# UART_to_RS232.net
KiCad netlist of a schematic drawn in EAGLE
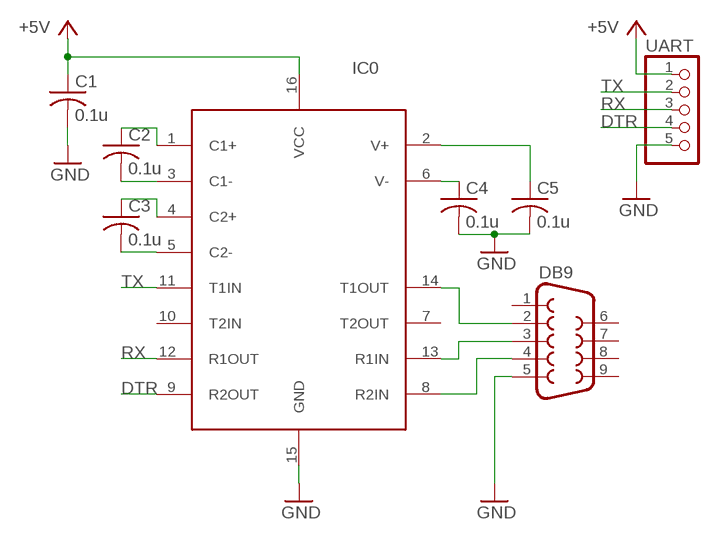
[diagram p0: schematic, sheet 1]

(export (version "E")
  (design (tool "Eeschema 10.0.6"))
  (components
    (comp (ref "C1")
      (value "0.1u")
      (footprint "eagle-import:C0805K")
      (libsource (lib "eagle-import") (part "C-USC0805K"))
    )
    (comp (ref "C2")
      (value "0.1u")
      (footprint "eagle-import:C0805K")
      (libsource (lib "eagle-import") (part "C-USC0805K"))
    )
    (comp (ref "C3")
      (value "0.1u")
      (footprint "eagle-import:C0805K")
      (libsource (lib "eagle-import") (part "C-USC0805K"))
    )
    (comp (ref "C4")
      (value "0.1u")
      (footprint "eagle-import:C0805K")
      (libsource (lib "eagle-import") (part "C-USC0805K"))
    )
    (comp (ref "C5")
      (value "0.1u")
      (footprint "eagle-import:C0805K")
      (libsource (lib "eagle-import") (part "C-USC0805K"))
    )
    (comp (ref "DB9")
      (value "F09HP")
      (footprint "eagle-import:F09HP")
      (libsource (lib "eagle-import") (part "F09HP"))
    )
    (comp (ref "IC0")
      (value "ICL3232")
      (footprint "eagle-import:SO16")
      (libsource (lib "eagle-import") (part "ICL3232"))
    )
    (comp (ref "UART")
      (value "PINHD-1X5")
      (footprint "eagle-import:1X05")
      (libsource (lib "eagle-import") (part "PINHD-1X5"))
    )
  )
  (nets
    (net (code "1") (name "+5V") (class "Default")
      (node (ref "C1") (pin "1") (pinfunction "1_1") (pintype "passive"))
      (node (ref "IC0") (pin "16") (pinfunction "VCC_16") (pintype "power_in"))
      (node (ref "UART") (pin "1") (pinfunction "1_1") (pintype "passive"))
    )
    (net (code "2") (name "/DTR") (class "Default")
      (node (ref "IC0") (pin "9") (pinfunction "R2OUT_9") (pintype "bidirectional"))
      (node (ref "UART") (pin "4") (pinfunction "4_4") (pintype "passive"))
    )
    (net (code "3") (name "/RX") (class "Default")
      (node (ref "IC0") (pin "12") (pinfunction "R1OUT_12") (pintype "bidirectional"))
      (node (ref "UART") (pin "3") (pinfunction "3_3") (pintype "passive"))
    )
    (net (code "4") (name "/TX") (class "Default")
      (node (ref "IC0") (pin "11") (pinfunction "T1IN_11") (pintype "bidirectional"))
      (node (ref "UART") (pin "2") (pinfunction "2_2") (pintype "passive"))
    )
    (net (code "5") (name "GND") (class "Default")
      (node (ref "C1") (pin "2") (pinfunction "2_2") (pintype "passive"))
      (node (ref "C4") (pin "2") (pinfunction "2_2") (pintype "passive"))
      (node (ref "C5") (pin "2") (pinfunction "2_2") (pintype "passive"))
      (node (ref "DB9") (pin "5") (pinfunction "5_5") (pintype "passive"))
      (node (ref "IC0") (pin "15") (pinfunction "GND_15") (pintype "power_in"))
      (node (ref "UART") (pin "5") (pinfunction "5_5") (pintype "passive"))
    )
    (net (code "6") (name "Net-(IC0-C1+)") (class "Default")
      (node (ref "C2") (pin "1") (pinfunction "1_1") (pintype "passive"))
      (node (ref "IC0") (pin "1") (pinfunction "C1+_1") (pintype "bidirectional"))
    )
    (net (code "7") (name "Net-(IC0-C1-)") (class "Default")
      (node (ref "C2") (pin "2") (pinfunction "2_2") (pintype "passive"))
      (node (ref "IC0") (pin "3") (pinfunction "C1-_3") (pintype "bidirectional"))
    )
    (net (code "8") (name "Net-(IC0-C2+)") (class "Default")
      (node (ref "C3") (pin "1") (pinfunction "1_1") (pintype "passive"))
      (node (ref "IC0") (pin "4") (pinfunction "C2+_4") (pintype "bidirectional"))
    )
    (net (code "9") (name "Net-(IC0-C2-)") (class "Default")
      (node (ref "C3") (pin "2") (pinfunction "2_2") (pintype "passive"))
      (node (ref "IC0") (pin "5") (pinfunction "C2-_5") (pintype "bidirectional"))
    )
    (net (code "10") (name "Net-(IC0-R1IN)") (class "Default")
      (node (ref "DB9") (pin "3") (pinfunction "3_3") (pintype "passive"))
      (node (ref "IC0") (pin "13") (pinfunction "R1IN_13") (pintype "bidirectional"))
    )
    (net (code "11") (name "Net-(IC0-R2IN)") (class "Default")
      (node (ref "DB9") (pin "4") (pinfunction "4_4") (pintype "passive"))
      (node (ref "IC0") (pin "8") (pinfunction "R2IN_8") (pintype "bidirectional"))
    )
    (net (code "12") (name "Net-(IC0-T1OUT)") (class "Default")
      (node (ref "DB9") (pin "2") (pinfunction "2_2") (pintype "passive"))
      (node (ref "IC0") (pin "14") (pinfunction "T1OUT_14") (pintype "bidirectional"))
    )
    (net (code "13") (name "Net-(IC0-V+)") (class "Default")
      (node (ref "C5") (pin "1") (pinfunction "1_1") (pintype "passive"))
      (node (ref "IC0") (pin "2") (pinfunction "V+_2") (pintype "bidirectional"))
    )
    (net (code "14") (name "Net-(IC0-V-)") (class "Default")
      (node (ref "C4") (pin "1") (pinfunction "1_1") (pintype "passive"))
      (node (ref "IC0") (pin "6") (pinfunction "V-_6") (pintype "bidirectional"))
    )
    (net (code "15") (name "unconnected-(DB9-Pad1)") (class "Default")
      (node (ref "DB9") (pin "1") (pinfunction "1_1") (pintype "passive"))
    )
    (net (code "16") (name "unconnected-(DB9-Pad6)") (class "Default")
      (node (ref "DB9") (pin "6") (pinfunction "6_6") (pintype "passive"))
    )
    (net (code "17") (name "unconnected-(DB9-Pad7)") (class "Default")
      (node (ref "DB9") (pin "7") (pinfunction "7_7") (pintype "passive"))
    )
    (net (code "18") (name "unconnected-(DB9-Pad8)") (class "Default")
      (node (ref "DB9") (pin "8") (pinfunction "8_8") (pintype "passive"))
    )
    (net (code "19") (name "unconnected-(DB9-Pad9)") (class "Default")
      (node (ref "DB9") (pin "9") (pinfunction "9_9") (pintype "passive"))
    )
    (net (code "20") (name "unconnected-(IC0-T2IN-Pad10)") (class "Default")
      (node (ref "IC0") (pin "10") (pinfunction "T2IN_10") (pintype "bidirectional"))
    )
    (net (code "21") (name "unconnected-(IC0-T2OUT-Pad7)") (class "Default")
      (node (ref "IC0") (pin "7") (pinfunction "T2OUT_7") (pintype "bidirectional"))
    )
  )
)
